# main_schem.net
KiCad netlist of a schematic drawn in EAGLE
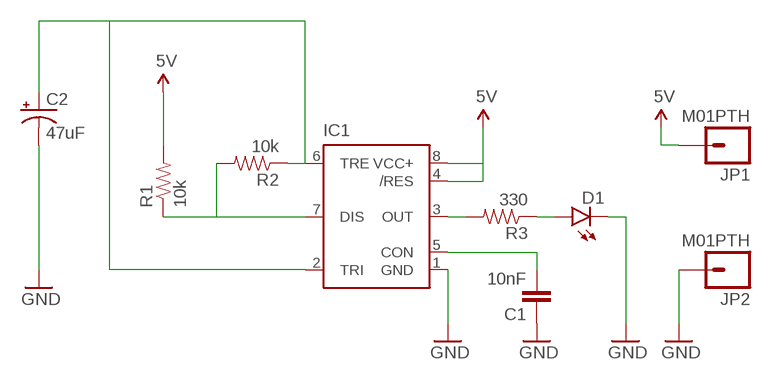
[diagram p0: schematic, sheet 1]

(export (version "E")
  (design (tool "Eeschema 10.0.6"))
  (components
    (comp (ref "C1")
      (value "10nF")
      (footprint "eagle-import:CAP-PTH-SMALL")
      (libsource (lib "eagle-import") (part "CAPPTH"))
    )
    (comp (ref "C2")
      (value "47uF")
      (footprint "eagle-import:CPOL-RADIAL-10UF-25V")
      (libsource (lib "eagle-import") (part "CAP_POLPTH2"))
    )
    (comp (ref "D1")
      (value "LED5MM")
      (footprint "eagle-import:LED5MM")
      (libsource (lib "eagle-import") (part "LED5MM"))
    )
    (comp (ref "IC1")
      (value "NE555KIT")
      (footprint "eagle-import:DIP08-KIT")
      (libsource (lib "eagle-import") (part "NE555KIT"))
    )
    (comp (ref "JP1")
      (value "M01PTH")
      (footprint "eagle-import:1X01")
      (libsource (lib "eagle-import") (part "M01PTH"))
    )
    (comp (ref "JP2")
      (value "M01PTH")
      (footprint "eagle-import:1X01")
      (libsource (lib "eagle-import") (part "M01PTH"))
    )
    (comp (ref "R1")
      (value "10k")
      (footprint "eagle-import:AXIAL-0.3")
      (libsource (lib "eagle-import") (part "10KOHM-1/4W5%(PTH)"))
    )
    (comp (ref "R2")
      (value "10k")
      (footprint "eagle-import:AXIAL-0.3")
      (libsource (lib "eagle-import") (part "10KOHM-1/4W5%(PTH)"))
    )
    (comp (ref "R3")
      (value "330")
      (footprint "eagle-import:AXIAL-0.3")
      (libsource (lib "eagle-import") (part "10KOHM-1/4W5%(PTH)"))
    )
  )
  (nets
    (net (code "1") (name "5V") (class "Default")
      (node (ref "IC1") (pin "4") (pinfunction "/RES_4") (pintype "input"))
      (node (ref "IC1") (pin "8") (pinfunction "VCC+_8") (pintype "power_in"))
      (node (ref "JP1") (pin "1") (pinfunction "1_1") (pintype "passive"))
      (node (ref "R1") (pin "P$2") (pinfunction "2_P$2") (pintype "passive"))
    )
    (net (code "2") (name "GND") (class "Default")
      (node (ref "C1") (pin "1") (pinfunction "1_1") (pintype "passive"))
      (node (ref "C2") (pin "2") (pinfunction "-_2") (pintype "passive"))
      (node (ref "D1") (pin "K") (pinfunction "C_K") (pintype "passive"))
      (node (ref "IC1") (pin "1") (pinfunction "GND_1") (pintype "power_in"))
      (node (ref "JP2") (pin "1") (pinfunction "1_1") (pintype "passive"))
    )
    (net (code "3") (name "Net-(C2-+)") (class "Default")
      (node (ref "C2") (pin "1") (pinfunction "+_1") (pintype "passive"))
      (node (ref "IC1") (pin "2") (pinfunction "TRI_2") (pintype "input"))
      (node (ref "IC1") (pin "6") (pinfunction "TRE_6") (pintype "input"))
      (node (ref "R2") (pin "P$1") (pinfunction "1_P$1") (pintype "passive"))
    )
    (net (code "4") (name "Net-(IC1-CON)") (class "Default")
      (node (ref "C1") (pin "2") (pinfunction "2_2") (pintype "passive"))
      (node (ref "IC1") (pin "5") (pinfunction "CON_5") (pintype "input"))
    )
    (net (code "5") (name "Net-(IC1-DIS)") (class "Default")
      (node (ref "IC1") (pin "7") (pinfunction "DIS_7") (pintype "input"))
      (node (ref "R1") (pin "P$1") (pinfunction "1_P$1") (pintype "passive"))
      (node (ref "R2") (pin "P$2") (pinfunction "2_P$2") (pintype "passive"))
    )
    (net (code "6") (name "Net-(IC1-OUT)") (class "Default")
      (node (ref "IC1") (pin "3") (pinfunction "OUT_3") (pintype "output"))
      (node (ref "R3") (pin "P$2") (pinfunction "2_P$2") (pintype "passive"))
    )
    (net (code "7") (name "Net-(R3-1)") (class "Default")
      (node (ref "D1") (pin "A") (pinfunction "A_A") (pintype "passive"))
      (node (ref "R3") (pin "P$1") (pinfunction "1_P$1") (pintype "passive"))
    )
  )
)
